# RESET-SWITCHES.net
KiCad netlist of a schematic drawn in Altium Designer
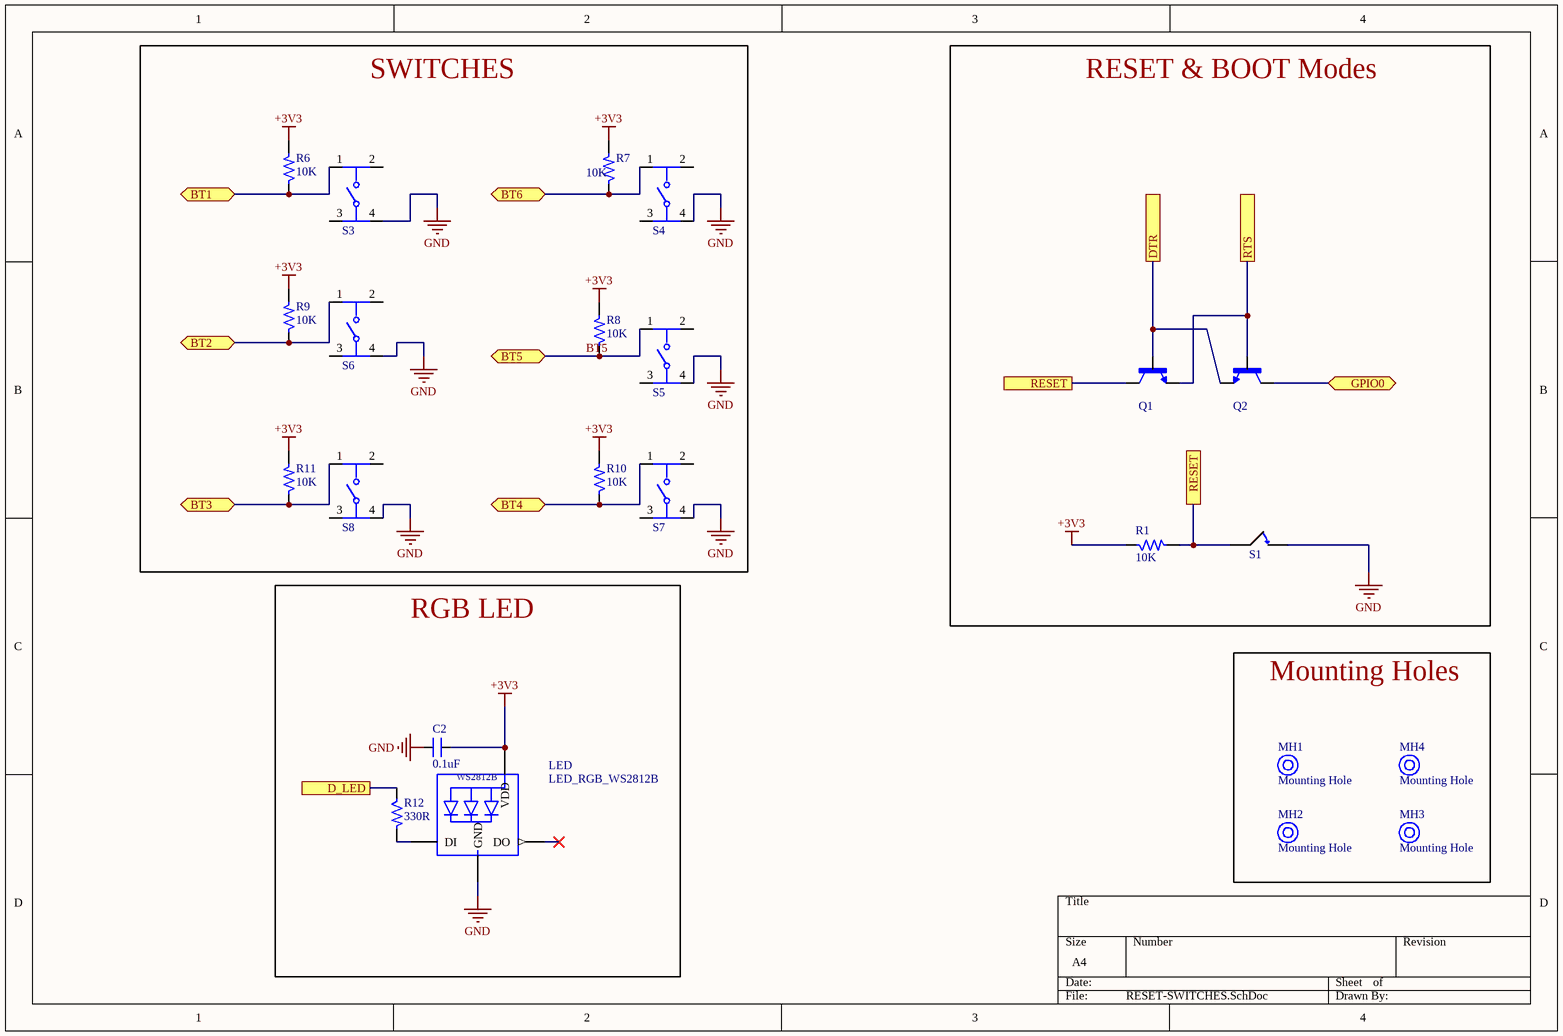
[diagram p0: RESET-SWITCHES.SchDoc]

(export (version "E")
  (design (tool "Eeschema 10.0.6"))
  (components
    (comp (ref "C2")
      (value "0.1uF")
      (footprint "CAP_0805")
      (description "0.1µF ±10% 50V Ceramic Capacitor X7R 0805 (2012 Metric)")
      (fields
        (field (name "MANUFACTURER") "Samsung")
        (field (name "MANUFACTURER PART NUMBER") "CL21B104KBCNNNC")
      )
      (libsource (lib "NOUMANPCBLIB") (part "CAP_0.1uF-50V-10%-0805"))
    )
    (comp (ref "LED")
      (value "LED_RGB_WS2812B")
      (footprint "WS2812B")
      (description "Raspberry Pi HAT _40 pin_ Wheeled Robotics Kit")
      (fields (field (name "MP") "WS2812B") (field (name "MF") "SparkFun Electronics"))
      (libsource (lib "NOUMANPCBLIB") (part "LED_RGB_WS2812B"))
    )
    (comp (ref "MH1")
      (value "Mounting Hole")
      (footprint "MOUNTING-NO-COPPER")
      (fields (field (name "MANUFACTURER PART NUMBER") "NA"))
      (libsource (lib "NOUMANPCBLIB") (part "MH_3H_ONLY_1"))
    )
    (comp (ref "MH2")
      (value "Mounting Hole")
      (footprint "MOUNTING-NO-COPPER")
      (fields (field (name "MANUFACTURER PART NUMBER") "NA"))
      (libsource (lib "NOUMANPCBLIB") (part "MH_3H_ONLY_1"))
    )
    (comp (ref "MH3")
      (value "Mounting Hole")
      (footprint "MOUNTING-NO-COPPER")
      (fields (field (name "MANUFACTURER PART NUMBER") "NA"))
      (libsource (lib "NOUMANPCBLIB") (part "MH_3H_ONLY_1"))
    )
    (comp (ref "MH4")
      (value "Mounting Hole")
      (footprint "MOUNTING-NO-COPPER")
      (fields (field (name "MANUFACTURER PART NUMBER") "NA"))
      (libsource (lib "NOUMANPCBLIB") (part "MH_3H_ONLY_1"))
    )
    (comp (ref "Q1")
      (value "TRANS_NPN_SS8050-G")
      (footprint "TRANS_NPN_SS8050-G")
      (description "Bipolar (BJT) Transistor NPN 25 V 1.5 A 100MHz 300 mW Surface Mount SOT-23-3")
      (libsource (lib "") (part "TRANS_NPN_SS8050-G_1"))
    )
    (comp (ref "Q2")
      (value "TRANS_NPN_SS8050-G")
      (footprint "TRANS_NPN_SS8050-G")
      (description "Bipolar (BJT) Transistor NPN 25 V 1.5 A 100MHz 300 mW Surface Mount SOT-23-3")
      (libsource (lib "NOUMANPCBLIB") (part "TRANS_NPN_SS8050-G"))
    )
    (comp (ref "R1")
      (value "10K")
      (footprint "RES_0805")
      (description "10 kOhms ±1% 0.125W, 1/8W Chip Resistor 0805 (2012 Metric) Automotive AEC-Q200 Thick Film")
      (fields (field (name "MANUFACTURER") "CTS") (field (name "MANUFACTURER PART NUMBER") "WR08X1002FTL"))
      (libsource (lib "NOUMANPCBLIB") (part "RES_10K-0.125W-1%-0805"))
    )
    (comp (ref "R6")
      (value "10K")
      (footprint "RES_0805")
      (description "10 kOhms ±1% 0.125W, 1/8W Chip Resistor 0805 (2012 Metric) Automotive AEC-Q200 Thick Film")
      (fields (field (name "MANUFACTURER") "CTS") (field (name "MANUFACTURER PART NUMBER") "WR08X1002FTL"))
      (libsource (lib "NOUMANPCBLIB") (part "RES_10K-0.125W-1%-0805"))
    )
    (comp (ref "R7")
      (value "10K")
      (footprint "RES_0805")
      (description "10 kOhms ±1% 0.125W, 1/8W Chip Resistor 0805 (2012 Metric) Automotive AEC-Q200 Thick Film")
      (fields (field (name "MANUFACTURER") "CTS") (field (name "MANUFACTURER PART NUMBER") "WR08X1002FTL"))
      (libsource (lib "NOUMANPCBLIB") (part "RES_10K-0.125W-1%-0805"))
    )
    (comp (ref "R8")
      (value "10K")
      (footprint "RES_0805")
      (description "10 kOhms ±1% 0.125W, 1/8W Chip Resistor 0805 (2012 Metric) Automotive AEC-Q200 Thick Film")
      (fields (field (name "MANUFACTURER") "CTS") (field (name "MANUFACTURER PART NUMBER") "WR08X1002FTL"))
      (libsource (lib "NOUMANPCBLIB") (part "RES_10K-0.125W-1%-0805"))
    )
    (comp (ref "R9")
      (value "10K")
      (footprint "RES_0805")
      (description "10 kOhms ±1% 0.125W, 1/8W Chip Resistor 0805 (2012 Metric) Automotive AEC-Q200 Thick Film")
      (fields (field (name "MANUFACTURER") "CTS") (field (name "MANUFACTURER PART NUMBER") "WR08X1002FTL"))
      (libsource (lib "NOUMANPCBLIB") (part "RES_10K-0.125W-1%-0805"))
    )
    (comp (ref "R10")
      (value "10K")
      (footprint "RES_0805")
      (description "10 kOhms ±1% 0.125W, 1/8W Chip Resistor 0805 (2012 Metric) Automotive AEC-Q200 Thick Film")
      (fields (field (name "MANUFACTURER") "CTS") (field (name "MANUFACTURER PART NUMBER") "WR08X1002FTL"))
      (libsource (lib "NOUMANPCBLIB") (part "RES_10K-0.125W-1%-0805"))
    )
    (comp (ref "R11")
      (value "10K")
      (footprint "RES_0805")
      (description "10 kOhms ±1% 0.125W, 1/8W Chip Resistor 0805 (2012 Metric) Automotive AEC-Q200 Thick Film")
      (fields (field (name "MANUFACTURER") "CTS") (field (name "MANUFACTURER PART NUMBER") "WR08X1002FTL"))
      (libsource (lib "NOUMANPCBLIB") (part "RES_10K-0.125W-1%-0805"))
    )
    (comp (ref "R12")
      (value "330R")
      (footprint "RES_0805")
      (description "330 Ohms ±1% 0.125W, 1/8W Chip Resistor 0805 (2012 Metric) Automotive AEC-Q200 Thick Film")
      (fields (field (name "MANUFACTURER") "Walsin") (field (name "MANUFACTURER PART NUMBER") "WR08X3300FTL"))
      (libsource (lib "NOUMANPCBLIB") (part "RES_330R-0.125W-1%-0805"))
    )
    (comp (ref "S1")
      (value "Button Tactile Switch, NO 0.05 A 0.8mm")
      (footprint "Button8014X17N")
      (fields
        (field (name "MANUFACTURER") "C & K")
        (field (name "MANUFACTURER PART NO.") "B3F1000")
        (field (name "CREATOR") "R Kanjee")
      )
      (libsource (lib "Omron Tactile Switches") (part "Button Tactile Switch, NO 0.05 A 0.8mm"))
    )
    (comp (ref "S3")
      (value "SW_TACTILE_PTS645SM43SMTR92LFS")
      (footprint "C&K_0_MFG - duplicate")
      (libsource (lib "NOUMANPCBLIB") (part "SW_TACTILE_PTS645SM43SMTR92LFS"))
    )
    (comp (ref "S4")
      (value "SW_TACTILE_PTS645SM43SMTR92LFS")
      (footprint "C&K_0_MFG - duplicate")
      (libsource (lib "NOUMANPCBLIB") (part "SW_TACTILE_PTS645SM43SMTR92LFS"))
    )
    (comp (ref "S5")
      (value "SW_TACTILE_PTS645SM43SMTR92LFS")
      (footprint "C&K_0_MFG - duplicate")
      (libsource (lib "NOUMANPCBLIB") (part "SW_TACTILE_PTS645SM43SMTR92LFS"))
    )
    (comp (ref "S6")
      (value "SW_TACTILE_PTS645SM43SMTR92LFS")
      (footprint "C&K_0_MFG - duplicate")
      (libsource (lib "NOUMANPCBLIB") (part "SW_TACTILE_PTS645SM43SMTR92LFS"))
    )
    (comp (ref "S7")
      (value "SW_TACTILE_PTS645SM43SMTR92LFS")
      (footprint "C&K_0_MFG - duplicate")
      (libsource (lib "NOUMANPCBLIB") (part "SW_TACTILE_PTS645SM43SMTR92LFS"))
    )
    (comp (ref "S8")
      (value "SW_TACTILE_PTS645SM43SMTR92LFS")
      (footprint "C&K_0_MFG - duplicate")
      (libsource (lib "NOUMANPCBLIB") (part "SW_TACTILE_PTS645SM43SMTR92LFS"))
    )
  )
  (nets
    (net (code "1") (name "+3V3") (class "Default")
      (node (ref "C2") (pin "2") (pinfunction "2_2") (pintype "passive"))
      (node (ref "LED") (pin "1-VDD") (pinfunction "VDD_1-VDD") (pintype "power_in"))
      (node (ref "R1") (pin "1") (pinfunction "1_1") (pintype "passive"))
      (node (ref "R10") (pin "2") (pinfunction "2_2") (pintype "passive"))
      (node (ref "R11") (pin "2") (pinfunction "2_2") (pintype "passive"))
      (node (ref "R6") (pin "2") (pinfunction "2_2") (pintype "passive"))
      (node (ref "R7") (pin "2") (pinfunction "2_2") (pintype "passive"))
      (node (ref "R8") (pin "2") (pinfunction "2_2") (pintype "passive"))
      (node (ref "R9") (pin "2") (pinfunction "2_2") (pintype "passive"))
    )
    (net (code "2") (name "/BT1") (class "Default")
      (node (ref "R6") (pin "1") (pinfunction "1_1") (pintype "passive"))
      (node (ref "S3") (pin "1") (pinfunction "1_1") (pintype "passive"))
    )
    (net (code "3") (name "/BT2") (class "Default")
      (node (ref "R9") (pin "1") (pinfunction "1_1") (pintype "passive"))
      (node (ref "S6") (pin "1") (pinfunction "1_1") (pintype "passive"))
    )
    (net (code "4") (name "/BT3") (class "Default")
      (node (ref "R11") (pin "1") (pinfunction "1_1") (pintype "passive"))
      (node (ref "S8") (pin "1") (pinfunction "1_1") (pintype "passive"))
    )
    (net (code "5") (name "/BT4") (class "Default")
      (node (ref "R10") (pin "1") (pinfunction "1_1") (pintype "passive"))
      (node (ref "S7") (pin "1") (pinfunction "1_1") (pintype "passive"))
    )
    (net (code "6") (name "/BT5") (class "Default")
      (node (ref "R8") (pin "1") (pinfunction "1_1") (pintype "passive"))
      (node (ref "S5") (pin "1") (pinfunction "1_1") (pintype "passive"))
    )
    (net (code "7") (name "/BT6") (class "Default")
      (node (ref "R7") (pin "1") (pinfunction "1_1") (pintype "passive"))
      (node (ref "S4") (pin "1") (pinfunction "1_1") (pintype "passive"))
    )
    (net (code "8") (name "/DTR") (class "Default")
      (node (ref "Q1") (pin "1") (pinfunction "B_1") (pintype "passive"))
      (node (ref "Q2") (pin "2") (pinfunction "E_2") (pintype "passive"))
    )
    (net (code "9") (name "/D_LED") (class "Default")
      (node (ref "R12") (pin "1") (pinfunction "1_1") (pintype "passive"))
    )
    (net (code "10") (name "/GPIO0") (class "Default")
      (node (ref "Q2") (pin "3") (pinfunction "C_3") (pintype "passive"))
    )
    (net (code "11") (name "/RESET") (class "Default")
      (node (ref "Q1") (pin "3") (pinfunction "C_3") (pintype "passive"))
      (node (ref "R1") (pin "2") (pinfunction "2_2") (pintype "passive"))
      (node (ref "S1") (pin "1") (pinfunction "1_1") (pintype "passive"))
    )
    (net (code "12") (name "/RTS") (class "Default")
      (node (ref "Q1") (pin "2") (pinfunction "E_2") (pintype "passive"))
      (node (ref "Q2") (pin "1") (pinfunction "B_1") (pintype "passive"))
    )
    (net (code "13") (name "GND") (class "Default")
      (node (ref "C2") (pin "1") (pinfunction "1_1") (pintype "passive"))
      (node (ref "LED") (pin "3-GND") (pinfunction "GND_3-GND") (pintype "power_in"))
      (node (ref "S1") (pin "2") (pinfunction "2_2") (pintype "passive"))
      (node (ref "S3") (pin "4") (pinfunction "4_4") (pintype "passive"))
      (node (ref "S4") (pin "4") (pinfunction "4_4") (pintype "passive"))
      (node (ref "S5") (pin "4") (pinfunction "4_4") (pintype "passive"))
      (node (ref "S6") (pin "4") (pinfunction "4_4") (pintype "passive"))
      (node (ref "S7") (pin "4") (pinfunction "4_4") (pintype "passive"))
      (node (ref "S8") (pin "4") (pinfunction "4_4") (pintype "passive"))
    )
    (net (code "14") (name "Net-(LED-DI)") (class "Default")
      (node (ref "LED") (pin "4-DIN") (pinfunction "DI_4-DIN") (pintype "passive"))
      (node (ref "R12") (pin "2") (pinfunction "2_2") (pintype "passive"))
    )
    (net (code "15") (name "unconnected-(LED-DO-Pad2-DOUT)") (class "Default")
      (node (ref "LED") (pin "2-DOUT") (pinfunction "DO_2-DOUT") (pintype "output+no_connect"))
    )
    (net (code "16") (name "unconnected-(S3-Pad2)") (class "Default")
      (node (ref "S3") (pin "2") (pinfunction "2_2") (pintype "passive"))
    )
    (net (code "17") (name "unconnected-(S3-Pad3)") (class "Default")
      (node (ref "S3") (pin "3") (pinfunction "3_3") (pintype "passive"))
    )
    (net (code "18") (name "unconnected-(S4-Pad2)") (class "Default")
      (node (ref "S4") (pin "2") (pinfunction "2_2") (pintype "passive"))
    )
    (net (code "19") (name "unconnected-(S4-Pad3)") (class "Default")
      (node (ref "S4") (pin "3") (pinfunction "3_3") (pintype "passive"))
    )
    (net (code "20") (name "unconnected-(S5-Pad2)") (class "Default")
      (node (ref "S5") (pin "2") (pinfunction "2_2") (pintype "passive"))
    )
    (net (code "21") (name "unconnected-(S5-Pad3)") (class "Default")
      (node (ref "S5") (pin "3") (pinfunction "3_3") (pintype "passive"))
    )
    (net (code "22") (name "unconnected-(S6-Pad2)") (class "Default")
      (node (ref "S6") (pin "2") (pinfunction "2_2") (pintype "passive"))
    )
    (net (code "23") (name "unconnected-(S6-Pad3)") (class "Default")
      (node (ref "S6") (pin "3") (pinfunction "3_3") (pintype "passive"))
    )
    (net (code "24") (name "unconnected-(S7-Pad2)") (class "Default")
      (node (ref "S7") (pin "2") (pinfunction "2_2") (pintype "passive"))
    )
    (net (code "25") (name "unconnected-(S7-Pad3)") (class "Default")
      (node (ref "S7") (pin "3") (pinfunction "3_3") (pintype "passive"))
    )
    (net (code "26") (name "unconnected-(S8-Pad2)") (class "Default")
      (node (ref "S8") (pin "2") (pinfunction "2_2") (pintype "passive"))
    )
    (net (code "27") (name "unconnected-(S8-Pad3)") (class "Default")
      (node (ref "S8") (pin "3") (pinfunction "3_3") (pintype "passive"))
    )
  )
)
